# mainPower.net
KiCad netlist of a schematic drawn in Altium Designer
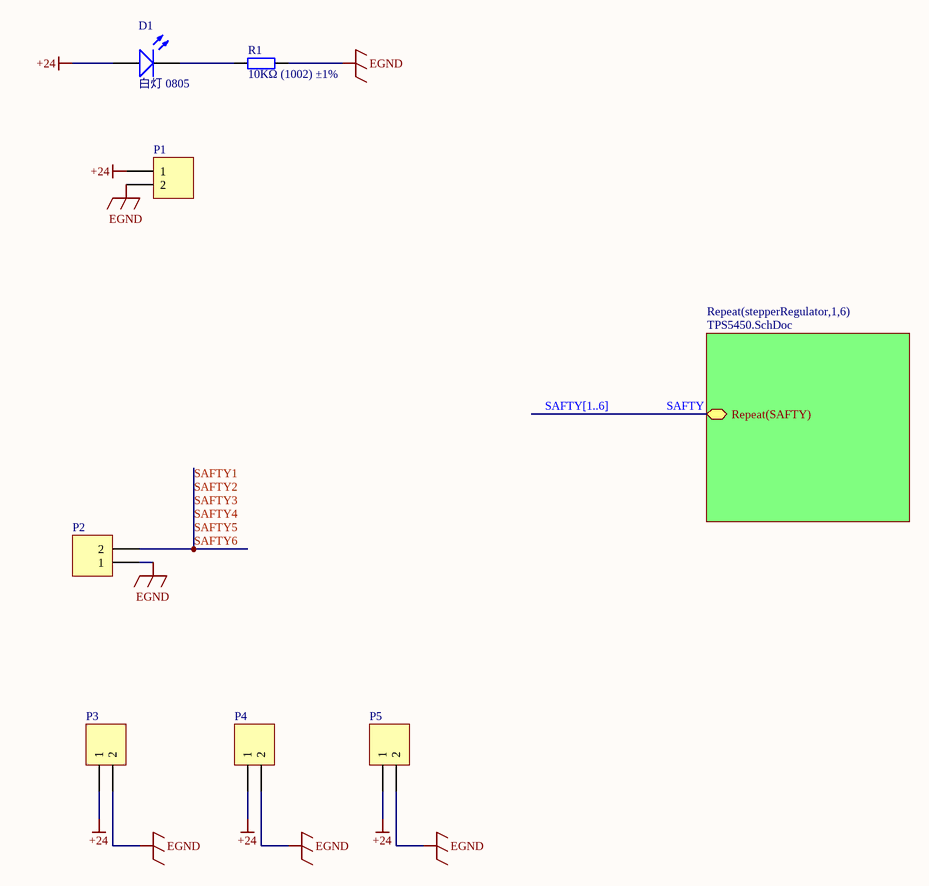
[diagram p0: mainPower.SchDoc]

(export (version "E")
  (design (tool "Eeschema 10.0.6"))
  (components
    (comp (ref "D1")
      (value "白灯 0805")
      (footprint "0805_LED_S1")
      (description "发光二极管")
      (libsource (lib "LED") (part "0805 白灯"))
    )
    (comp (ref "P1")
      (value "Header 2")
      (footprint "5.08-2P")
      (description "Header, 2-Pin")
      (fields (field (name "PUBLISHER") "Altium Limited"))
      (libsource (lib "") (part "Header 2_2"))
    )
    (comp (ref "P2")
      (value "Header 2")
      (footprint "5.08-2P")
      (description "Header, 2-Pin")
      (fields (field (name "PUBLISHER") "Altium Limited"))
      (libsource (lib "") (part "Header 2_1"))
    )
    (comp (ref "P3")
      (value "Header 2")
      (footprint "XH-2A")
      (description "Header, 2-Pin")
      (fields (field (name "PUBLISHER") "Altium Limited"))
      (libsource (lib "Sparks") (part "Header 2"))
    )
    (comp (ref "P4")
      (value "Header 2")
      (footprint "XH-2A")
      (description "Header, 2-Pin")
      (fields (field (name "PUBLISHER") "Altium Limited"))
      (libsource (lib "Sparks") (part "Header 2"))
    )
    (comp (ref "P5")
      (value "Header 2")
      (footprint "XH-2A")
      (description "Header, 2-Pin")
      (fields (field (name "PUBLISHER") "Altium Limited"))
      (libsource (lib "Sparks") (part "Header 2"))
    )
    (comp (ref "R1")
      (value "10KΩ (1002) ±1%")
      (footprint "0805_R")
      (description "贴片电阻")
      (libsource (lib "Miscellaneous Devices LC") (part "0805 10KΩ (1002) 1%"))
    )
  )
  (nets
    (net (code "1") (name "+24") (class "Default")
      (node (ref "D1") (pin "A") (pinfunction "A_A") (pintype "passive"))
      (node (ref "P1") (pin "1") (pinfunction "1_1") (pintype "passive"))
      (node (ref "P3") (pin "1") (pinfunction "1_1") (pintype "passive"))
      (node (ref "P4") (pin "1") (pinfunction "1_1") (pintype "passive"))
      (node (ref "P5") (pin "1") (pinfunction "1_1") (pintype "passive"))
    )
    (net (code "3") (name "/SAFTY6") (class "Default")
      (node (ref "P2") (pin "2") (pinfunction "2_2") (pintype "passive"))
    )
    (net (code "5") (name "EGND") (class "Default")
      (node (ref "P1") (pin "2") (pinfunction "2_2") (pintype "passive"))
      (node (ref "P2") (pin "1") (pinfunction "1_1") (pintype "passive"))
      (node (ref "P3") (pin "2") (pinfunction "2_2") (pintype "passive"))
      (node (ref "P4") (pin "2") (pinfunction "2_2") (pintype "passive"))
      (node (ref "P5") (pin "2") (pinfunction "2_2") (pintype "passive"))
      (node (ref "R1") (pin "2") (pinfunction "2_2") (pintype "passive"))
    )
    (net (code "6") (name "Net-(D1-PadK)") (class "Default")
      (node (ref "D1") (pin "K") (pinfunction "K_K") (pintype "passive"))
      (node (ref "R1") (pin "1") (pinfunction "1_1") (pintype "passive"))
    )
  )
)
